# Power.net
KiCad netlist of a schematic drawn in Altium Designer
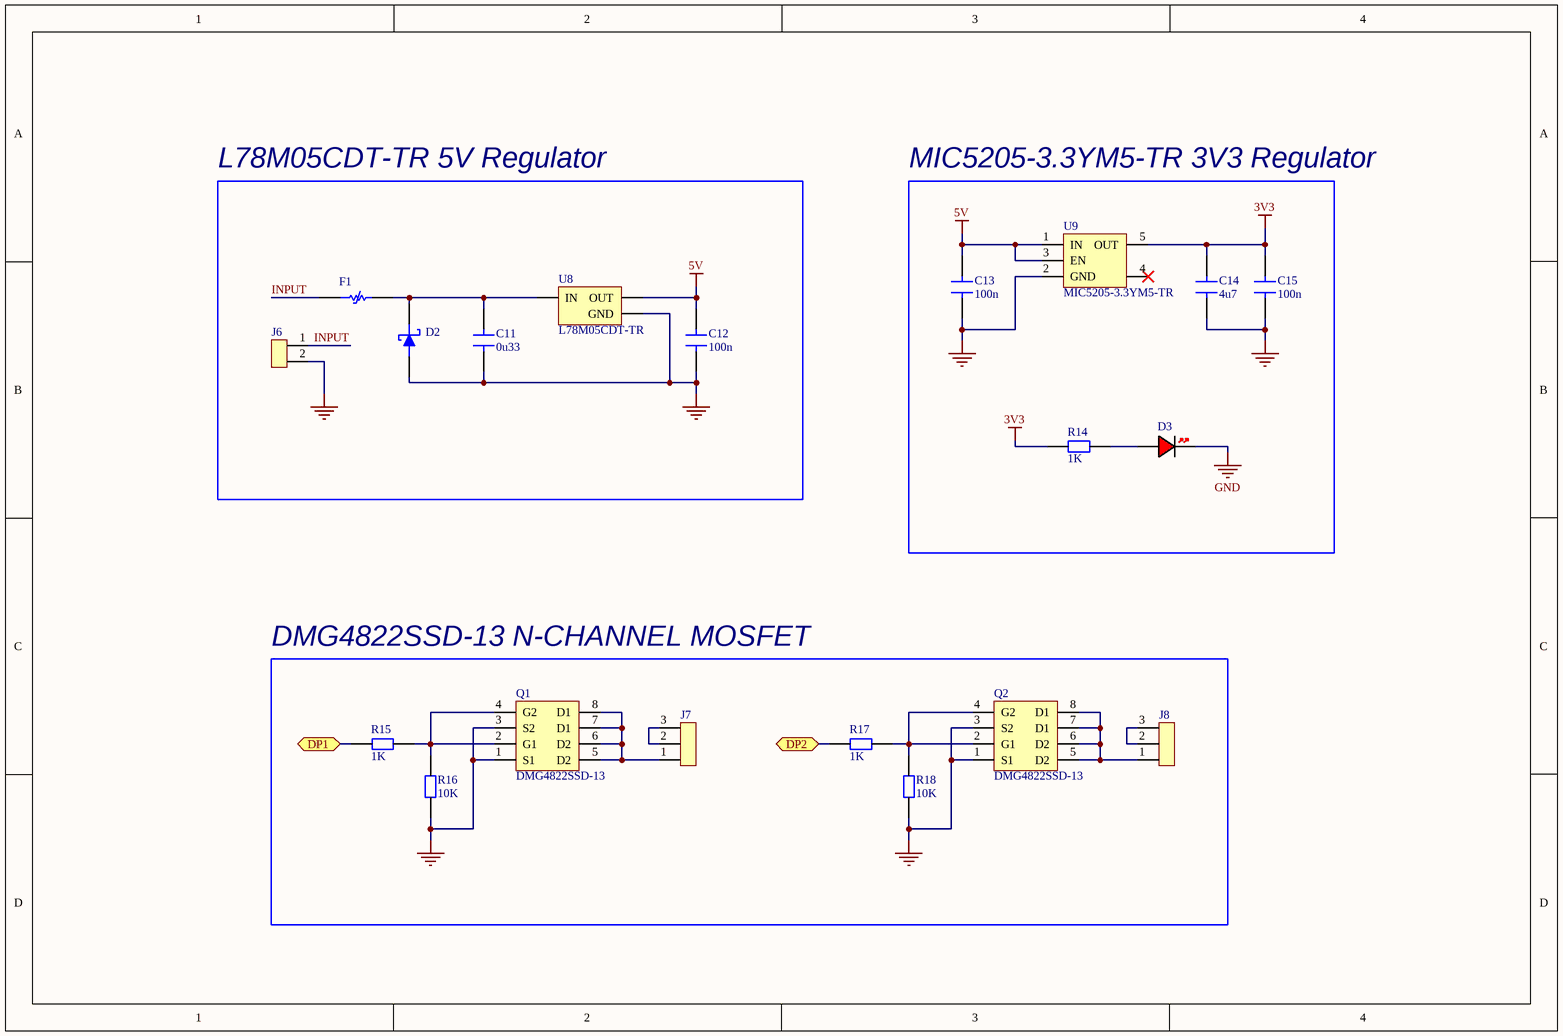
[diagram p0: Power.SchDoc]

(export (version "E")
  (design (tool "Eeschema 10.0.6"))
  (components
    (comp (ref "C11")
      (value "0u33")
      (footprint "CAP 0805")
      (description "Capacitor SMD 0805 50V")
      (libsource (lib "Schlib") (part "CAP 0805 50V"))
    )
    (comp (ref "C12")
      (value "100n")
      (footprint "CAP 0805")
      (description "Capacitor SMD 0805 50V")
      (libsource (lib "Schlib") (part "CAP 0805 50V"))
    )
    (comp (ref "C13")
      (value "100n")
      (footprint "CAP 0805")
      (description "Capacitor SMD 0805 50V")
      (libsource (lib "Schlib") (part "CAP 0805 50V"))
    )
    (comp (ref "C14")
      (value "4u7")
      (footprint "CAP 0805")
      (description "Capacitor SMD 0805 50V")
      (libsource (lib "Schlib") (part "CAP 0805 50V"))
    )
    (comp (ref "C15")
      (value "100n")
      (footprint "CAP 0805")
      (description "Capacitor SMD 0805 50V")
      (libsource (lib "Schlib") (part "CAP 0805 50V"))
    )
    (comp (ref "D2")
      (value "SMBJ12CA-13-F")
      (footprint "SMBJ12CA-13-F")
      (description "TVS DIODE 12VWM 19.9VC SMB")
      (fields (field (name "MANUFACTURER") "Diodes"))
      (libsource (lib "Schlib") (part "SMBJ12CA-13-F"))
    )
    (comp (ref "D3")
      (value "LED 0805 RED")
      (footprint "LED 0805 RED")
      (description "LED 0805 RED SMD")
      (libsource (lib "Schlib") (part "LED 0805 RED"))
    )
    (comp (ref "F1")
      (value "0ZCG0075FF2C")
      (footprint "0ZCG0075FF2C")
      (fields (field (name "MANUFACTURER") "Bel"))
      (libsource (lib "Schlib") (part "0ZCG0075FF2C"))
    )
    (comp (ref "J6")
      (value "KF301 2P Terminal")
      (footprint "KF301 2P")
      (description "2 Pin Screw Terminal Block 5mm")
      (libsource (lib "Schlib") (part "KF301 2P Terminal"))
    )
    (comp (ref "J7")
      (value "KF301 3P Terminal")
      (footprint "KF301 3P")
      (description "3 Pin Screw Terminal Block 5mm")
      (libsource (lib "Schlib") (part "KF301 3P Terminal"))
    )
    (comp (ref "J8")
      (value "KF301 3P Terminal")
      (footprint "KF301 3P")
      (description "3 Pin Screw Terminal Block 5mm")
      (libsource (lib "Schlib") (part "KF301 3P Terminal"))
    )
    (comp (ref "Q1")
      (value "DMG4822SSD-13")
      (footprint "DMG4822SSD-13")
      (description "Dual N-Channel 30 V 1.42 W 10.5 nC Enhancement Mode Mosfet - SOIC-8")
      (fields (field (name "MANUFACTURER") "Diodes"))
      (libsource (lib "Schlib") (part "DMG4822SSD-13"))
    )
    (comp (ref "Q2")
      (value "DMG4822SSD-13")
      (footprint "DMG4822SSD-13")
      (description "Dual N-Channel 30 V 1.42 W 10.5 nC Enhancement Mode Mosfet - SOIC-8")
      (fields (field (name "MANUFACTURER") "Diodes"))
      (libsource (lib "Schlib") (part "DMG4822SSD-13"))
    )
    (comp (ref "R14")
      (value "1K")
      (footprint "RES 0603")
      (description "Resistor SMD 0603")
      (libsource (lib "Schlib") (part "RES 0603"))
    )
    (comp (ref "R15")
      (value "1K")
      (footprint "RES 0603")
      (description "Resistor SMD 0603")
      (libsource (lib "Schlib") (part "RES 0603"))
    )
    (comp (ref "R16")
      (value "10K")
      (footprint "RES 0603")
      (description "Resistor SMD 0603")
      (libsource (lib "Schlib") (part "RES 0603"))
    )
    (comp (ref "R17")
      (value "1K")
      (footprint "RES 0603")
      (description "Resistor SMD 0603")
      (libsource (lib "Schlib") (part "RES 0603"))
    )
    (comp (ref "R18")
      (value "10K")
      (footprint "RES 0603")
      (description "Resistor SMD 0603")
      (libsource (lib "Schlib") (part "RES 0603"))
    )
    (comp (ref "U8")
      (value "L78M05CDT-TR")
      (footprint "L78M05CDT-TR")
      (description "IC REG LDO 5V 0.5A DPAK")
      (fields (field (name "MANUFACTURER") "STMicroelectronics") (field (name "TOLERANCE") "5%"))
      (libsource (lib "Schlib") (part "L78M05CDT-TR"))
    )
    (comp (ref "U9")
      (value "MIC5205-3.3YM5-TR")
      (footprint "MIC5205-3.3YM5-TR")
      (description "Linear Voltage Regulator IC Positive Fixed 1 Output 3.3V 150mA SOT-23-5")
      (fields (field (name "MANUFACTURER") "Microchip"))
      (libsource (lib "Schlib") (part "MIC5205-3.3YM5-TR"))
    )
  )
  (nets
    (net (code "1") (name "/DP1") (class "Default")
      (node (ref "R15") (pin "1") (pinfunction "1_1") (pintype "passive"))
    )
    (net (code "2") (name "/DP2") (class "Default")
      (node (ref "R17") (pin "1") (pinfunction "1_1") (pintype "passive"))
    )
    (net (code "3") (name "/INPUT") (class "Default")
      (node (ref "F1") (pin "1") (pintype "passive"))
      (node (ref "J6") (pin "1") (pinfunction "1_1") (pintype "passive"))
    )
    (net (code "4") (name "3V3") (class "Default")
      (node (ref "C14") (pin "2") (pinfunction "2_2") (pintype "passive"))
      (node (ref "C15") (pin "2") (pinfunction "2_2") (pintype "passive"))
      (node (ref "R14") (pin "1") (pinfunction "1_1") (pintype "passive"))
      (node (ref "U9") (pin "5") (pinfunction "OUT_5") (pintype "passive"))
    )
    (net (code "5") (name "5V") (class "Default")
      (node (ref "C12") (pin "2") (pinfunction "2_2") (pintype "passive"))
      (node (ref "C13") (pin "2") (pinfunction "2_2") (pintype "passive"))
      (node (ref "U8") (pin "3") (pinfunction "OUT_3") (pintype "passive"))
      (node (ref "U9") (pin "1") (pinfunction "IN_1") (pintype "passive"))
      (node (ref "U9") (pin "3") (pinfunction "EN_3") (pintype "passive"))
    )
    (net (code "6") (name "GND") (class "Default")
      (node (ref "C11") (pin "1") (pinfunction "1_1") (pintype "passive"))
      (node (ref "C12") (pin "1") (pinfunction "1_1") (pintype "passive"))
      (node (ref "C13") (pin "1") (pinfunction "1_1") (pintype "passive"))
      (node (ref "C14") (pin "1") (pinfunction "1_1") (pintype "passive"))
      (node (ref "C15") (pin "1") (pinfunction "1_1") (pintype "passive"))
      (node (ref "D2") (pin "1") (pintype "passive"))
      (node (ref "D3") (pin "K") (pinfunction "K_K") (pintype "passive"))
      (node (ref "J6") (pin "2") (pinfunction "2_2") (pintype "passive"))
      (node (ref "Q1") (pin "1") (pinfunction "S1_1") (pintype "passive"))
      (node (ref "Q1") (pin "3") (pinfunction "S2_3") (pintype "passive"))
      (node (ref "Q2") (pin "1") (pinfunction "S1_1") (pintype "passive"))
      (node (ref "Q2") (pin "3") (pinfunction "S2_3") (pintype "passive"))
      (node (ref "R16") (pin "1") (pinfunction "1_1") (pintype "passive"))
      (node (ref "R18") (pin "1") (pinfunction "1_1") (pintype "passive"))
      (node (ref "U8") (pin "2") (pinfunction "GND_2") (pintype "passive"))
      (node (ref "U9") (pin "2") (pinfunction "GND_2") (pintype "passive"))
    )
    (net (code "7") (name "Net-(D3-PadA)") (class "Default")
      (node (ref "D3") (pin "A") (pinfunction "A_A") (pintype "passive"))
      (node (ref "R14") (pin "2") (pinfunction "2_2") (pintype "passive"))
    )
    (net (code "8") (name "Net-(J7-Pad1)") (class "Default")
      (node (ref "J7") (pin "1") (pinfunction "1_1") (pintype "passive"))
      (node (ref "Q1") (pin "5") (pinfunction "D2_5") (pintype "passive"))
      (node (ref "Q1") (pin "6") (pinfunction "D2_6") (pintype "passive"))
      (node (ref "Q1") (pin "7") (pinfunction "D1_7") (pintype "passive"))
      (node (ref "Q1") (pin "8") (pinfunction "D1_8") (pintype "passive"))
    )
    (net (code "9") (name "Net-(J7-Pad2)") (class "Default")
      (node (ref "J7") (pin "2") (pinfunction "2_2") (pintype "passive"))
      (node (ref "J7") (pin "3") (pinfunction "3_3") (pintype "passive"))
    )
    (net (code "10") (name "Net-(J8-Pad1)") (class "Default")
      (node (ref "J8") (pin "1") (pinfunction "1_1") (pintype "passive"))
      (node (ref "Q2") (pin "5") (pinfunction "D2_5") (pintype "passive"))
      (node (ref "Q2") (pin "6") (pinfunction "D2_6") (pintype "passive"))
      (node (ref "Q2") (pin "7") (pinfunction "D1_7") (pintype "passive"))
      (node (ref "Q2") (pin "8") (pinfunction "D1_8") (pintype "passive"))
    )
    (net (code "11") (name "Net-(J8-Pad2)") (class "Default")
      (node (ref "J8") (pin "2") (pinfunction "2_2") (pintype "passive"))
      (node (ref "J8") (pin "3") (pinfunction "3_3") (pintype "passive"))
    )
    (net (code "12") (name "Net-(Q1-G1)") (class "Default")
      (node (ref "Q1") (pin "2") (pinfunction "G1_2") (pintype "passive"))
      (node (ref "Q1") (pin "4") (pinfunction "G2_4") (pintype "passive"))
      (node (ref "R15") (pin "2") (pinfunction "2_2") (pintype "passive"))
      (node (ref "R16") (pin "2") (pinfunction "2_2") (pintype "passive"))
    )
    (net (code "13") (name "Net-(Q2-G1)") (class "Default")
      (node (ref "Q2") (pin "2") (pinfunction "G1_2") (pintype "passive"))
      (node (ref "Q2") (pin "4") (pinfunction "G2_4") (pintype "passive"))
      (node (ref "R17") (pin "2") (pinfunction "2_2") (pintype "passive"))
      (node (ref "R18") (pin "2") (pinfunction "2_2") (pintype "passive"))
    )
    (net (code "14") (name "Net-(U8-IN)") (class "Default")
      (node (ref "C11") (pin "2") (pinfunction "2_2") (pintype "passive"))
      (node (ref "D2") (pin "2") (pintype "passive"))
      (node (ref "F1") (pin "2") (pintype "passive"))
      (node (ref "U8") (pin "1") (pinfunction "IN_1") (pintype "passive"))
    )
    (net (code "15") (name "unconnected-(U9-Pad4)") (class "Default")
      (node (ref "U9") (pin "4") (pintype "passive+no_connect"))
    )
  )
)
